# PDB.net
KiCad netlist of a schematic drawn in EAGLE
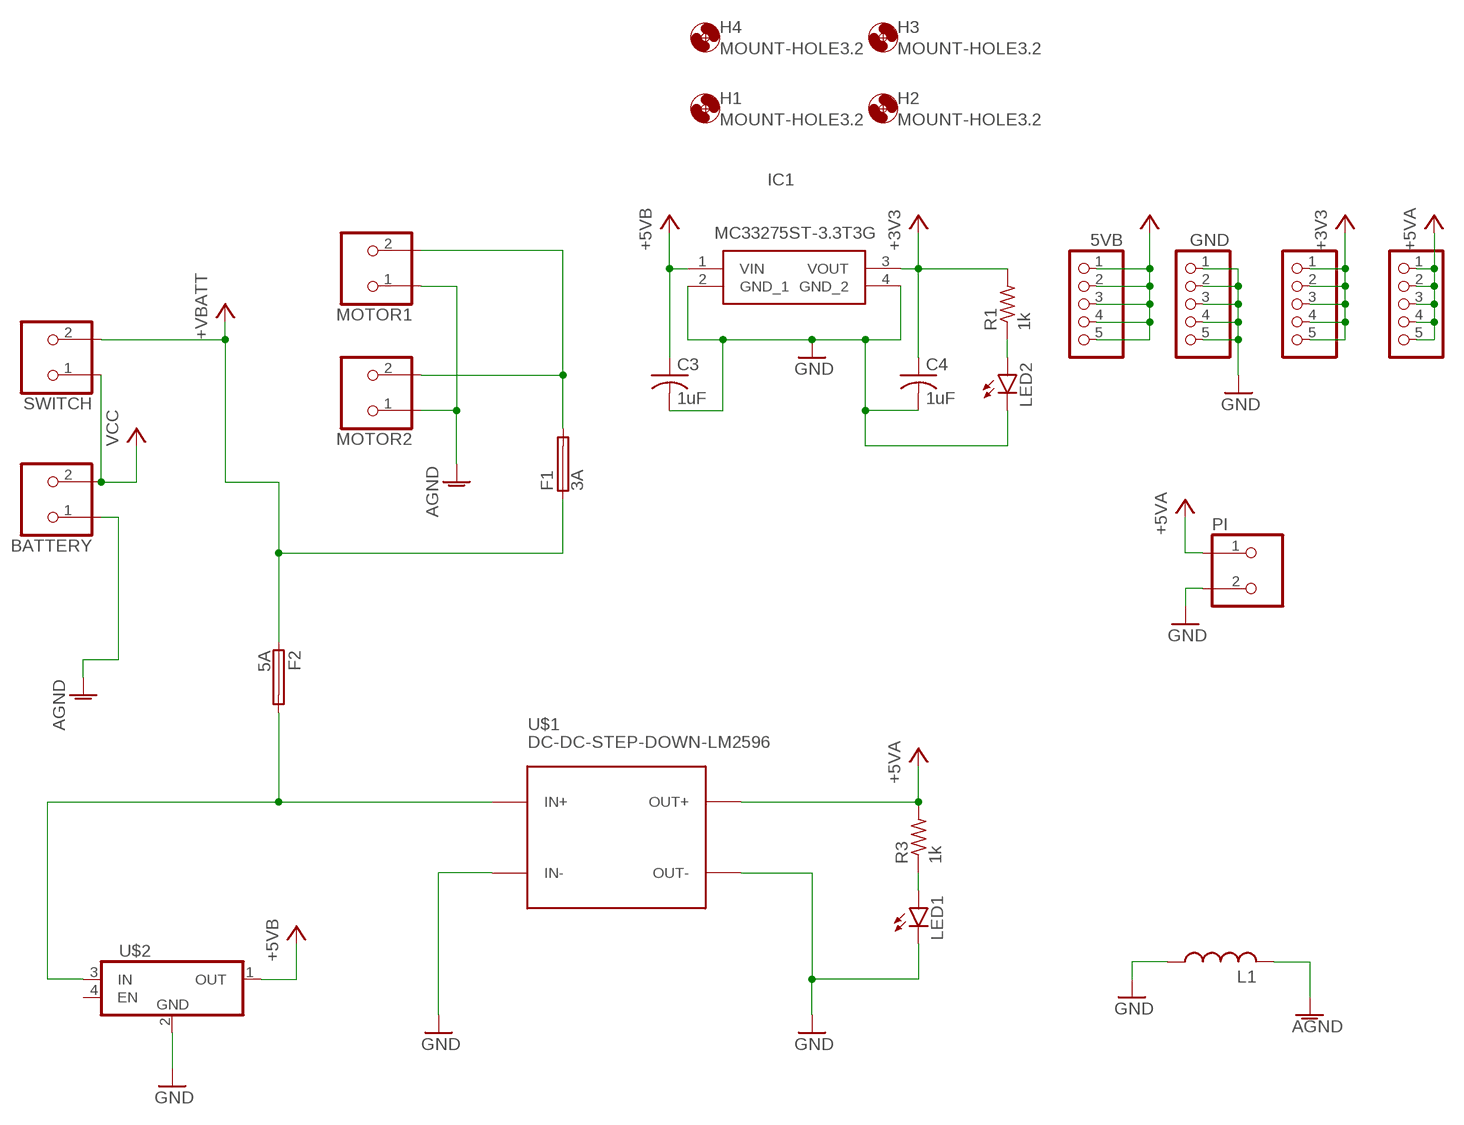
[diagram p0: schematic, sheet 1]

(export (version "E")
  (design (tool "Eeschema 10.0.6"))
  (components
    (comp (ref "3V3")
      (value "PINHD-1X5")
      (footprint "eagle-import:1X05")
      (libsource (lib "eagle-import") (part "PINHD-1X5"))
    )
    (comp (ref "5VA")
      (value "PINHD-1X5")
      (footprint "eagle-import:1X05")
      (libsource (lib "eagle-import") (part "PINHD-1X5"))
    )
    (comp (ref "5VB")
      (value "PINHD-1X5")
      (footprint "eagle-import:1X05")
      (libsource (lib "eagle-import") (part "PINHD-1X5"))
    )
    (comp (ref "BATTERY")
      (value "TERMINAL_2PINS")
      (footprint "eagle-import:TERMINAL_1X2")
      (libsource (lib "eagle-import") (part "TERMINAL_2PINS"))
    )
    (comp (ref "C3")
      (value "1uF")
      (footprint "eagle-import:C0805")
      (libsource (lib "eagle-import") (part "C-USC0805"))
    )
    (comp (ref "C4")
      (value "1uF")
      (footprint "eagle-import:C0805")
      (libsource (lib "eagle-import") (part "C-USC0805"))
    )
    (comp (ref "F1")
      (value "3A")
      (footprint "eagle-import:SH22,5A")
      (fields (field (name "MPN") "0031.7701.11"))
      (libsource (lib "eagle-import") (part "SH22,5A"))
    )
    (comp (ref "F2")
      (value "5A")
      (footprint "eagle-import:SH22,5A")
      (fields (field (name "MPN") "0031.7701.11"))
      (libsource (lib "eagle-import") (part "SH22,5A"))
    )
    (comp (ref "GND")
      (value "PINHD-1X5")
      (footprint "eagle-import:1X05")
      (libsource (lib "eagle-import") (part "PINHD-1X5"))
    )
    (comp (ref "H1")
      (value "MOUNT-HOLE3.2")
      (footprint "eagle-import:3,2")
      (libsource (lib "eagle-import") (part "MOUNT-HOLE3.2"))
    )
    (comp (ref "H2")
      (value "MOUNT-HOLE3.2")
      (footprint "eagle-import:3,2")
      (libsource (lib "eagle-import") (part "MOUNT-HOLE3.2"))
    )
    (comp (ref "H3")
      (value "MOUNT-HOLE3.2")
      (footprint "eagle-import:3,2")
      (libsource (lib "eagle-import") (part "MOUNT-HOLE3.2"))
    )
    (comp (ref "H4")
      (value "MOUNT-HOLE3.2")
      (footprint "eagle-import:3,2")
      (libsource (lib "eagle-import") (part "MOUNT-HOLE3.2"))
    )
    (comp (ref "IC1")
      (value "MC33275ST-3.3T3G")
      (footprint "eagle-import:SOT230P700X175-4N")
      (fields (field (name "MOUSER_PART_NUMBER") "863-MC33275ST-3.3T3G"))
      (libsource (lib "eagle-import") (part "MC33275ST-3.3T3G"))
    )
    (comp (ref "L1")
      (value "L-USL1812")
      (footprint "eagle-import:L1812")
      (libsource (lib "eagle-import") (part "L-USL1812"))
    )
    (comp (ref "LED1")
      (value "LED5MM")
      (footprint "eagle-import:LED5MM")
      (libsource (lib "eagle-import") (part "LED5MM"))
    )
    (comp (ref "LED2")
      (value "LED5MM")
      (footprint "eagle-import:LED5MM")
      (libsource (lib "eagle-import") (part "LED5MM"))
    )
    (comp (ref "MOTOR1")
      (value "TERMINAL_2PINS")
      (footprint "eagle-import:TERMINAL_1X2")
      (libsource (lib "eagle-import") (part "TERMINAL_2PINS"))
    )
    (comp (ref "MOTOR2")
      (value "TERMINAL_2PINS")
      (footprint "eagle-import:TERMINAL_1X2")
      (libsource (lib "eagle-import") (part "TERMINAL_2PINS"))
    )
    (comp (ref "PI")
      (value "TERMINAL_2PINS")
      (footprint "eagle-import:TERMINAL_1X2")
      (libsource (lib "eagle-import") (part "TERMINAL_2PINS"))
    )
    (comp (ref "R1")
      (value "1k")
      (footprint "eagle-import:R0805")
      (libsource (lib "eagle-import") (part "R-US_R0805"))
    )
    (comp (ref "R3")
      (value "1k")
      (footprint "eagle-import:R0805")
      (libsource (lib "eagle-import") (part "R-US_R0805"))
    )
    (comp (ref "SWITCH")
      (value "TERMINAL_2PINS")
      (footprint "eagle-import:TERMINAL_1X2")
      (libsource (lib "eagle-import") (part "TERMINAL_2PINS"))
    )
    (comp (ref "U$1")
      (value "DC-DC-STEP-DOWN-LM2596")
      (footprint "eagle-import:DC-DC-STEP-DOWN-LM2596")
      (libsource (lib "eagle-import") (part "DC-DC-STEP-DOWN-LM2596"))
    )
    (comp (ref "U$2")
      (value "DC-DC-STEP-DOWN-MP2315")
      (footprint "eagle-import:DC-DC-STEP-DOWN-MP2315")
      (libsource (lib "eagle-import") (part "DC-DC-STEP-DOWN-MP2315"))
    )
  )
  (nets
    (net (code "1") (name "+3V3") (class "Default")
      (node (ref "3V3") (pin "1") (pinfunction "1_1") (pintype "passive"))
      (node (ref "3V3") (pin "2") (pinfunction "2_2") (pintype "passive"))
      (node (ref "3V3") (pin "3") (pinfunction "3_3") (pintype "passive"))
      (node (ref "3V3") (pin "4") (pinfunction "4_4") (pintype "passive"))
      (node (ref "3V3") (pin "5") (pinfunction "5_5") (pintype "passive"))
      (node (ref "C4") (pin "1") (pinfunction "1_1") (pintype "passive"))
      (node (ref "IC1") (pin "3") (pinfunction "VOUT_3") (pintype "bidirectional"))
      (node (ref "R1") (pin "2") (pinfunction "2_2") (pintype "passive"))
    )
    (net (code "2") (name "+5VA") (class "Default")
      (node (ref "5VA") (pin "1") (pinfunction "1_1") (pintype "passive"))
      (node (ref "5VA") (pin "2") (pinfunction "2_2") (pintype "passive"))
      (node (ref "5VA") (pin "3") (pinfunction "3_3") (pintype "passive"))
      (node (ref "5VA") (pin "4") (pinfunction "4_4") (pintype "passive"))
      (node (ref "5VA") (pin "5") (pinfunction "5_5") (pintype "passive"))
      (node (ref "PI") (pin "1") (pinfunction "1_1") (pintype "passive"))
      (node (ref "R3") (pin "2") (pinfunction "2_2") (pintype "passive"))
      (node (ref "U$1") (pin "OUT+") (pinfunction "OUT+_OUT+") (pintype "bidirectional"))
    )
    (net (code "3") (name "+5VB") (class "Default")
      (node (ref "5VB") (pin "1") (pinfunction "1_1") (pintype "passive"))
      (node (ref "5VB") (pin "2") (pinfunction "2_2") (pintype "passive"))
      (node (ref "5VB") (pin "3") (pinfunction "3_3") (pintype "passive"))
      (node (ref "5VB") (pin "4") (pinfunction "4_4") (pintype "passive"))
      (node (ref "5VB") (pin "5") (pinfunction "5_5") (pintype "passive"))
      (node (ref "C3") (pin "1") (pinfunction "1_1") (pintype "passive"))
      (node (ref "IC1") (pin "1") (pinfunction "VIN_1") (pintype "bidirectional"))
      (node (ref "U$2") (pin "1") (pinfunction "OUT_1") (pintype "passive"))
    )
    (net (code "4") (name "+VBATT") (class "Default")
      (node (ref "F1") (pin "1") (pinfunction "1_1") (pintype "passive"))
      (node (ref "F2") (pin "1") (pinfunction "1_1") (pintype "passive"))
      (node (ref "SWITCH") (pin "2") (pinfunction "2_2") (pintype "passive"))
    )
    (net (code "5") (name "AGND") (class "Default")
      (node (ref "BATTERY") (pin "1") (pinfunction "1_1") (pintype "passive"))
      (node (ref "L1") (pin "2") (pinfunction "2_2") (pintype "passive"))
      (node (ref "MOTOR1") (pin "1") (pinfunction "1_1") (pintype "passive"))
      (node (ref "MOTOR2") (pin "1") (pinfunction "1_1") (pintype "passive"))
    )
    (net (code "6") (name "GND") (class "Default")
      (node (ref "C3") (pin "2") (pinfunction "2_2") (pintype "passive"))
      (node (ref "C4") (pin "2") (pinfunction "2_2") (pintype "passive"))
      (node (ref "GND") (pin "1") (pinfunction "1_1") (pintype "passive"))
      (node (ref "GND") (pin "2") (pinfunction "2_2") (pintype "passive"))
      (node (ref "GND") (pin "3") (pinfunction "3_3") (pintype "passive"))
      (node (ref "GND") (pin "4") (pinfunction "4_4") (pintype "passive"))
      (node (ref "GND") (pin "5") (pinfunction "5_5") (pintype "passive"))
      (node (ref "IC1") (pin "2") (pinfunction "GND_1_2") (pintype "bidirectional"))
      (node (ref "IC1") (pin "4") (pinfunction "GND_2_4") (pintype "bidirectional"))
      (node (ref "L1") (pin "1") (pinfunction "1_1") (pintype "passive"))
      (node (ref "LED1") (pin "K") (pinfunction "C_K") (pintype "passive"))
      (node (ref "LED2") (pin "K") (pinfunction "C_K") (pintype "passive"))
      (node (ref "PI") (pin "2") (pinfunction "2_2") (pintype "passive"))
      (node (ref "U$1") (pin "IN-") (pinfunction "IN-_IN-") (pintype "bidirectional"))
      (node (ref "U$1") (pin "OUT-") (pinfunction "OUT-_OUT-") (pintype "bidirectional"))
      (node (ref "U$2") (pin "2") (pinfunction "GND_2") (pintype "passive"))
    )
    (net (code "7") (name "Net-(F1-Pad2)") (class "Default")
      (node (ref "F1") (pin "2") (pinfunction "2_2") (pintype "passive"))
      (node (ref "MOTOR1") (pin "2") (pinfunction "2_2") (pintype "passive"))
      (node (ref "MOTOR2") (pin "2") (pinfunction "2_2") (pintype "passive"))
    )
    (net (code "8") (name "Net-(LED1-PadA)") (class "Default")
      (node (ref "LED1") (pin "A") (pinfunction "A_A") (pintype "passive"))
      (node (ref "R3") (pin "1") (pinfunction "1_1") (pintype "passive"))
    )
    (net (code "9") (name "Net-(LED2-PadA)") (class "Default")
      (node (ref "LED2") (pin "A") (pinfunction "A_A") (pintype "passive"))
      (node (ref "R1") (pin "1") (pinfunction "1_1") (pintype "passive"))
    )
    (net (code "10") (name "Net-(U$2-IN)") (class "Default")
      (node (ref "F2") (pin "2") (pinfunction "2_2") (pintype "passive"))
      (node (ref "U$1") (pin "IN+") (pinfunction "IN+_IN+") (pintype "bidirectional"))
      (node (ref "U$2") (pin "3") (pinfunction "IN_3") (pintype "input"))
    )
    (net (code "11") (name "VCC") (class "Default")
      (node (ref "BATTERY") (pin "2") (pinfunction "2_2") (pintype "passive"))
      (node (ref "SWITCH") (pin "1") (pinfunction "1_1") (pintype "passive"))
    )
    (net (code "12") (name "unconnected-(U$2-EN-Pad4)") (class "Default")
      (node (ref "U$2") (pin "4") (pinfunction "EN_4") (pintype "input"))
    )
  )
)
